# MCU-Board.net
KiCad netlist of a schematic drawn in Altium Designer
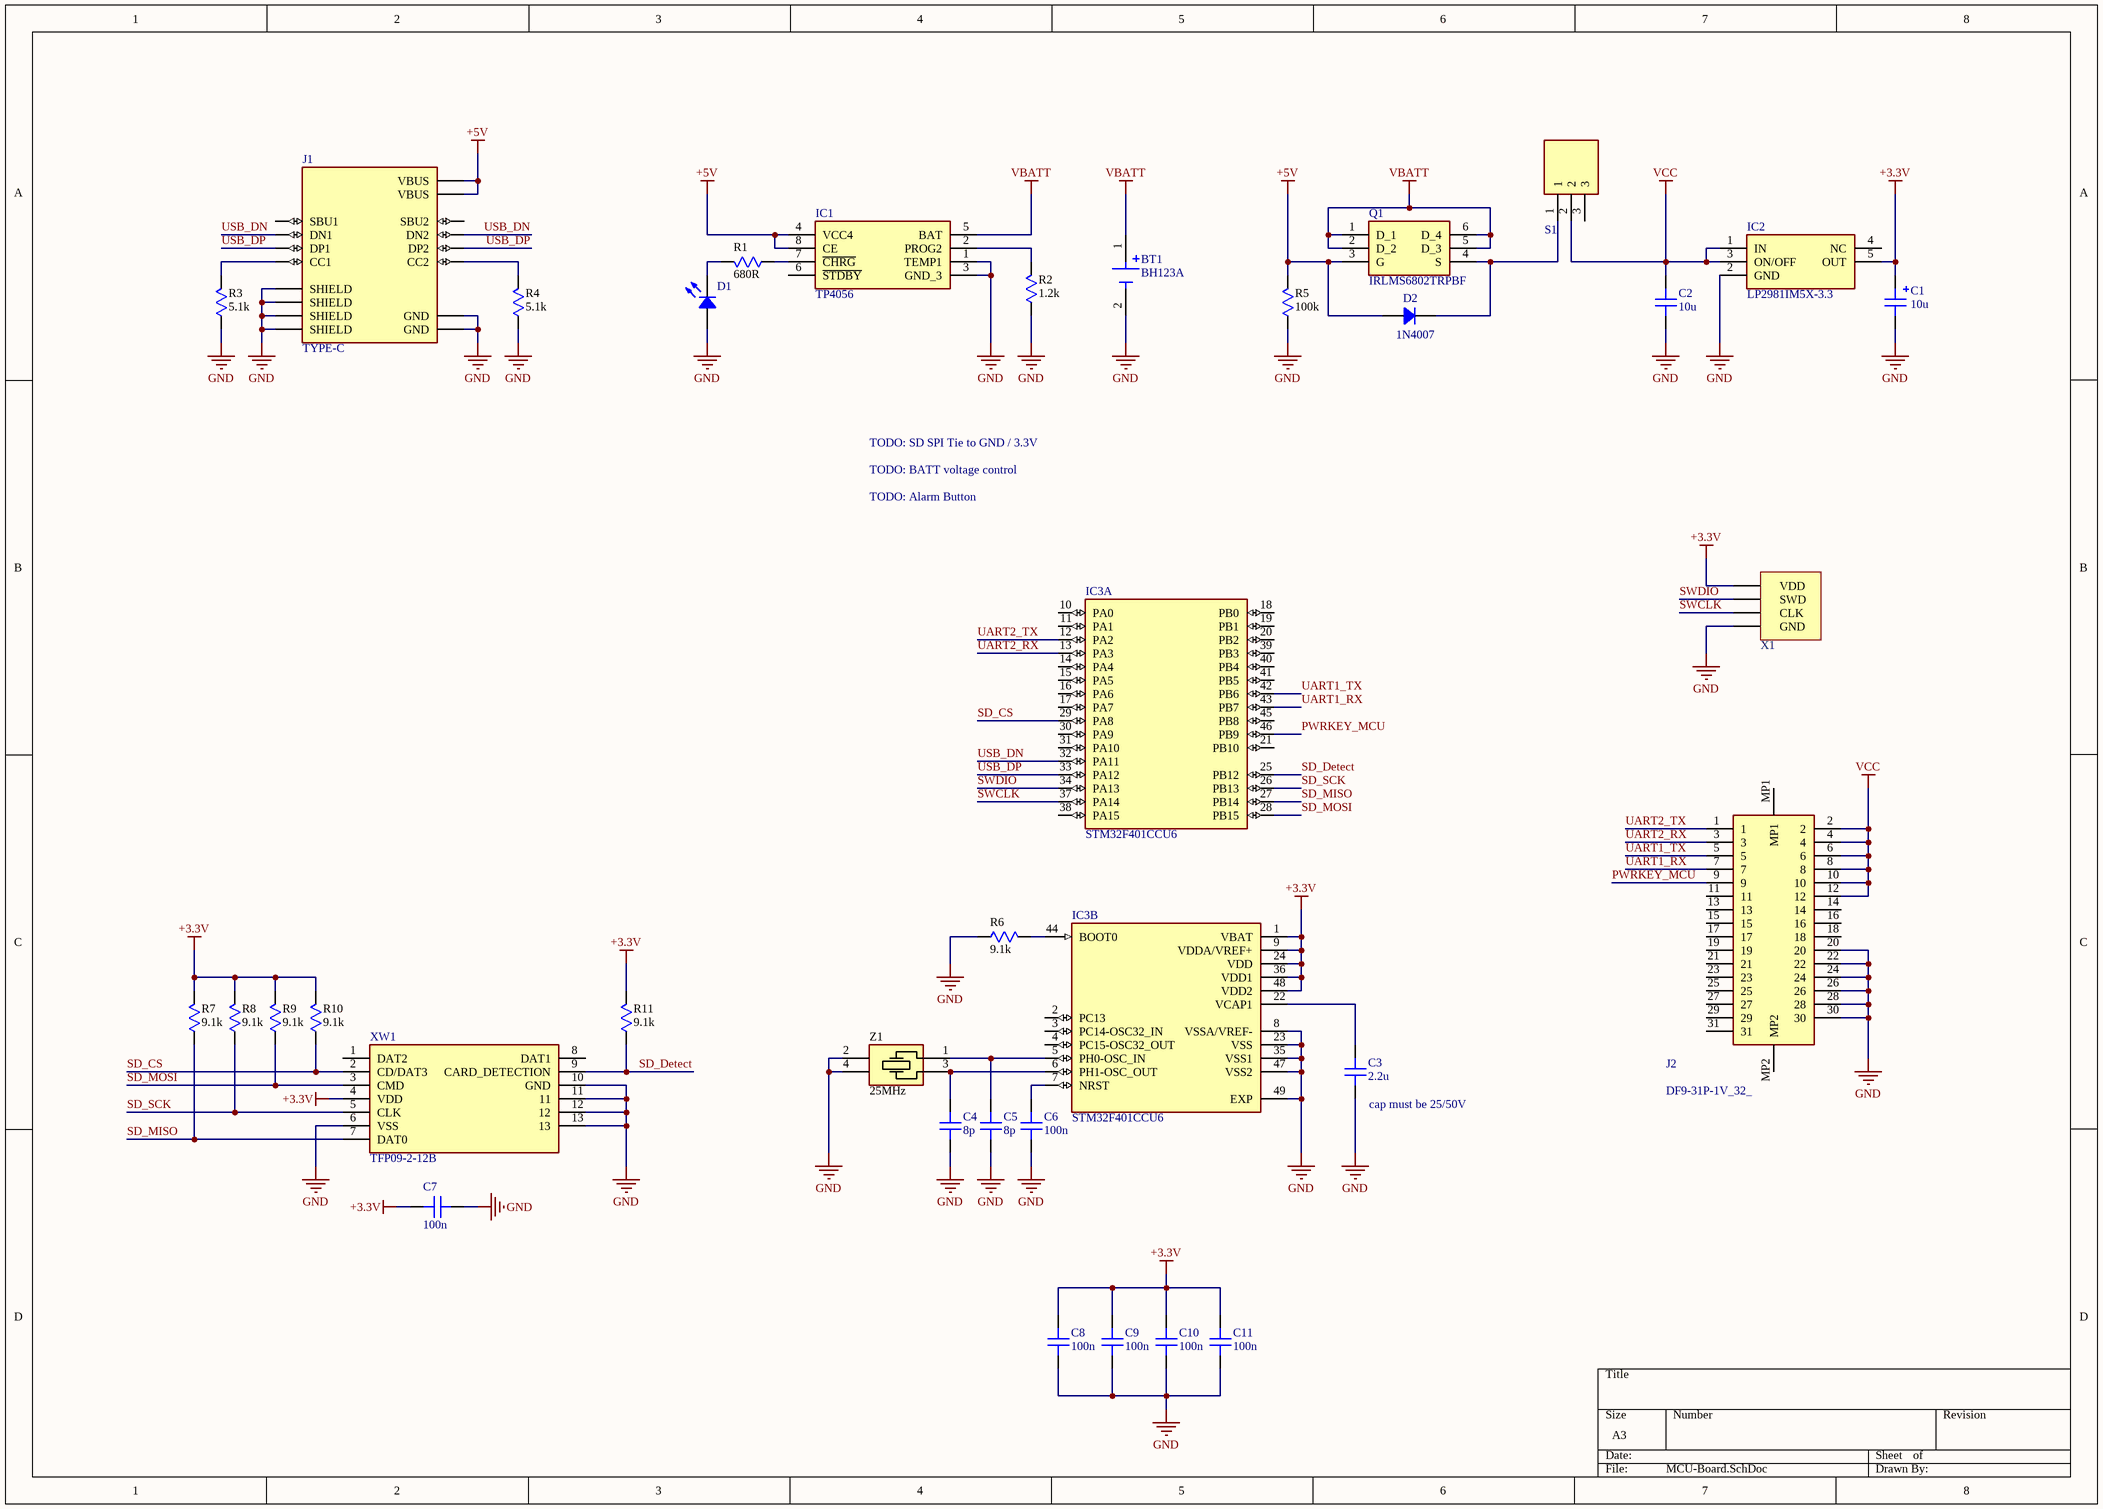
[diagram p0: MCU-Board.SchDoc]

(export (version "E")
  (design (tool "Eeschema 10.0.6"))
  (components
    (comp (ref "BT1")
      (value "BH123A")
      (footprint "BAT_BH123A")
      (description "BATTERY HOLDER CR123A PC PIN")
      (fields (field (name "MF") "MPD"))
      (libsource (lib "Schlib") (part "BH123A"))
    )
    (comp (ref "C1")
      (value "10u")
      (footprint "PcbLib:CAP: TANTAL-A")
      (description "SMD Capacitor Polar")
      (libsource (lib "Schlib") (part "Capacitor_polar"))
    )
    (comp (ref "C2")
      (value "10u")
      (footprint "PcbLib:CAP: 0805")
      (description "SMD Capacitor")
      (libsource (lib "Schlib") (part "Capacitor"))
    )
    (comp (ref "C3")
      (value "2.2u")
      (footprint "PcbLib:CAP: 0805")
      (description "SMD Capacitor")
      (libsource (lib "Schlib") (part "Capacitor"))
    )
    (comp (ref "C4")
      (value "8p")
      (footprint "PcbLib:CAP: 0603")
      (description "SMD Capacitor")
      (libsource (lib "Schlib") (part "Capacitor"))
    )
    (comp (ref "C5")
      (value "8p")
      (footprint "PcbLib:CAP: 0603")
      (description "SMD Capacitor")
      (libsource (lib "Schlib") (part "Capacitor"))
    )
    (comp (ref "C6")
      (value "100n")
      (footprint "PcbLib:CAP: 0603")
      (description "SMD Capacitor")
      (libsource (lib "Schlib") (part "Capacitor"))
    )
    (comp (ref "C7")
      (value "100n")
      (footprint "PcbLib:CAP: 0603")
      (description "SMD Capacitor")
      (libsource (lib "Schlib") (part "Capacitor"))
    )
    (comp (ref "C8")
      (value "100n")
      (footprint "PcbLib:CAP: 0603")
      (description "SMD Capacitor")
      (libsource (lib "Schlib") (part "Capacitor"))
    )
    (comp (ref "C9")
      (value "100n")
      (footprint "PcbLib:CAP: 0603")
      (description "SMD Capacitor")
      (libsource (lib "Schlib") (part "Capacitor"))
    )
    (comp (ref "C10")
      (value "100n")
      (footprint "PcbLib:CAP: 0603")
      (description "SMD Capacitor")
      (libsource (lib "Schlib") (part "Capacitor"))
    )
    (comp (ref "C11")
      (value "100n")
      (footprint "PcbLib:CAP: 0603")
      (description "SMD Capacitor")
      (libsource (lib "Schlib") (part "Capacitor"))
    )
    (comp (ref "D1")
      (value "~")
      (footprint "PcbLib:LED 0603_1608")
      (description "Chip LED")
      (libsource (lib "Schlib") (part "LED"))
    )
    (comp (ref "D2")
      (value "1N4007")
      (footprint "PcbLib:DIODE: SMA")
      (description "Rectifier Diode")
      (libsource (lib "Schlib") (part "Diode"))
    )
    (comp (ref "IC1")
      (value "TP4056")
      (footprint "PcbLib:SOIC127P600X175-9N")
      (description "Connector")
      (libsource (lib "Schlib") (part "TP4056"))
    )
    (comp (ref "IC2")
      (value "LP2981IM5X-3.3")
      (footprint "PcbLib:SOT95P280X145-5N")
      (description "Integrated Circuit")
      (fields
        (field (name "MANUFACTURER_PART_NUMBER") "LP2981IM5X-5.0")
        (field (name "MOUSER PART NUMBER") "926-LP2981IM5X-50")
      )
      (libsource (lib "Schlib") (part "LP2981IM5X-3.3"))
    )
    (comp (ref "IC3")
      (value "STM32F401CCU6")
      (footprint "PcbLib:QFN50P700X700X60-49N-D")
      (description "Integrated Circuit")
      (fields (field (name "MOUSER PART NUMBER") "511-STM32F401CCU6"))
      (libsource (lib "Schlib") (part "STM32F401CCU6"))
    )
    (comp (ref "J1")
      (value "TYPE-C")
      (footprint "PcbLib:HRO_TYPE-C-31-M-12")
      (description "USB Connectors 24 Receptacle 1 8.94*7.3mm RoHS")
      (fields (field (name "MP") "TYPE-C-31-M-12"))
      (libsource (lib "Schlib") (part "TYPE-C-31-M-12"))
    )
    (comp (ref "J2")
      (value "DF9-31P-1V_32_")
      (footprint "PcbLib:DF931P1V32")
      (description "Connector")
      (fields
        (field (name "MANUFACTURER_PART_NUMBER") "DF9-31P-1V(32)")
        (field (name "MOUSER PART NUMBER") "798-DF9-31P-1V32")
      )
      (libsource (lib "Schlib") (part "DF9-31P-1V_32_"))
    )
    (comp (ref "Q1")
      (value "IRLMS6802TRPBF")
      (footprint "PcbLib:SOT95P280X130-6N")
      (description "MOSFET (P-Channel)")
      (fields (field (name "MOUSER PART NUMBER") "942-IRLMS6802TRPBF"))
      (libsource (lib "Schlib") (part "IRLMS6802TRPBF"))
    )
    (comp (ref "R1")
      (value "680R")
      (footprint "PcbLib:RES: 0603")
      (fields
        (field (name "MANUFACTURER") "Yageo")
        (field (name "PARTNUMBER") "RC0201JR-07100RL")
        (field (name "VALUEMANUFACTURERPARTNUMBER") "Resistor film, 680R, , 0201, 0.05W, -55...+125°C")
      )
      (libsource (lib "Schlib") (part "Resistor"))
    )
    (comp (ref "R2")
      (value "1.2k")
      (footprint "PcbLib:RES: 0805")
      (fields
        (field (name "MANUFACTURER") "Yageo")
        (field (name "PARTNUMBER") "RC0201JR-07100RL")
        (field (name "VALUEMANUFACTURERPARTNUMBER") "Resistor film, 1.2k, , 0201, 0.05W, -55...+125°C")
      )
      (libsource (lib "Schlib") (part "Resistor"))
    )
    (comp (ref "R3")
      (value "5.1k")
      (footprint "PcbLib:RES: 0603")
      (fields
        (field (name "MANUFACTURER") "Yageo")
        (field (name "PARTNUMBER") "RC0201JR-07100RL")
        (field (name "VALUEMANUFACTURERPARTNUMBER") "Resistor film, 5.1k, , 0201, 0.05W, -55...+125°C")
      )
      (libsource (lib "Schlib") (part "Resistor"))
    )
    (comp (ref "R4")
      (value "5.1k")
      (footprint "PcbLib:RES: 0603")
      (fields
        (field (name "MANUFACTURER") "Yageo")
        (field (name "PARTNUMBER") "RC0201JR-07100RL")
        (field (name "VALUEMANUFACTURERPARTNUMBER") "Resistor film, 5.1k, , 0201, 0.05W, -55...+125°C")
      )
      (libsource (lib "Schlib") (part "Resistor"))
    )
    (comp (ref "R5")
      (value "100k")
      (footprint "PcbLib:RES: 0603")
      (fields
        (field (name "MANUFACTURER") "Yageo")
        (field (name "PARTNUMBER") "RC0201JR-07100RL")
        (field (name "VALUEMANUFACTURERPARTNUMBER") "Resistor film, 100k, , 0201, 0.05W, -55...+125°C")
      )
      (libsource (lib "Schlib") (part "Resistor"))
    )
    (comp (ref "R6")
      (value "9.1k")
      (footprint "PcbLib:RES: 0603")
      (fields
        (field (name "MANUFACTURER") "Yageo")
        (field (name "PARTNUMBER") "RC0201JR-07100RL")
        (field (name "VALUEMANUFACTURERPARTNUMBER") "Resistor film, 9.1k, , 0201, 0.05W, -55...+125°C")
      )
      (libsource (lib "Schlib") (part "Resistor"))
    )
    (comp (ref "R7")
      (value "9.1k")
      (footprint "PcbLib:RES: 0603")
      (fields
        (field (name "MANUFACTURER") "Yageo")
        (field (name "PARTNUMBER") "RC0201JR-07100RL")
        (field (name "VALUEMANUFACTURERPARTNUMBER") "Resistor film, 9.1k, , 0201, 0.05W, -55...+125°C")
      )
      (libsource (lib "Schlib") (part "Resistor"))
    )
    (comp (ref "R8")
      (value "9.1k")
      (footprint "PcbLib:RES: 0603")
      (fields
        (field (name "MANUFACTURER") "Yageo")
        (field (name "PARTNUMBER") "RC0201JR-07100RL")
        (field (name "VALUEMANUFACTURERPARTNUMBER") "Resistor film, 9.1k, , 0201, 0.05W, -55...+125°C")
      )
      (libsource (lib "Schlib") (part "Resistor"))
    )
    (comp (ref "R9")
      (value "9.1k")
      (footprint "PcbLib:RES: 0603")
      (fields
        (field (name "MANUFACTURER") "Yageo")
        (field (name "PARTNUMBER") "RC0201JR-07100RL")
        (field (name "VALUEMANUFACTURERPARTNUMBER") "Resistor film, 9.1k, , 0201, 0.05W, -55...+125°C")
      )
      (libsource (lib "Schlib") (part "Resistor"))
    )
    (comp (ref "R10")
      (value "9.1k")
      (footprint "PcbLib:RES: 0603")
      (fields
        (field (name "MANUFACTURER") "Yageo")
        (field (name "PARTNUMBER") "RC0201JR-07100RL")
        (field (name "VALUEMANUFACTURERPARTNUMBER") "Resistor film, 9.1k, , 0201, 0.05W, -55...+125°C")
      )
      (libsource (lib "Schlib") (part "Resistor"))
    )
    (comp (ref "R11")
      (value "9.1k")
      (footprint "PcbLib:RES: 0603")
      (fields
        (field (name "MANUFACTURER") "Yageo")
        (field (name "PARTNUMBER") "RC0201JR-07100RL")
        (field (name "VALUEMANUFACTURERPARTNUMBER") "Resistor film, 9.1k, , 0201, 0.05W, -55...+125°C")
      )
      (libsource (lib "Schlib") (part "Resistor"))
    )
    (comp (ref "S1")
      (value "OS102011MA1QN1")
      (footprint "PcbLib:OS102011MA1QN1")
      (description "Switch")
      (fields (field (name "MOUSER PART NUMBER") "611-OS102011MA1QN1"))
      (libsource (lib "Schlib") (part "OS102011MA1QN1"))
    )
    (comp (ref "X1")
      (value "~")
      (footprint "PcbLib:CON: PLS-4R")
      (description "SWD Interface")
      (libsource (lib "Schlib") (part "Connector SWD"))
    )
    (comp (ref "XW1")
      (value "TFP09-2-12B")
      (footprint "PcbLib:TFP09212B")
      (description "Connector")
      (libsource (lib "Schlib") (part "TFP09-2-12B"))
    )
    (comp (ref "Z1")
      (value "~")
      (footprint "PcbLib:OSC: 3225")
      (fields
        (field (name "MANUFACTURER") "Murata Electronics")
        (field (name "PARTNUMBER") "XRCGB25M000F0L00R0")
        (field (name "VALUEMANUFACTURERPARTNUMBER") "Crystal, 25MHz, 6pF, ±50ppm, case 2016, -30...+85°C")
        (field (name "FREQUENCY") "25MHz")
      )
      (libsource (lib "Schlib") (part "Crystal"))
    )
  )
  (nets
    (net (code "1") (name "+3.3V") (class "Default")
      (node (ref "C1") (pin "1") (pinfunction "1_1") (pintype "passive"))
      (node (ref "C10") (pin "2") (pinfunction "2_2") (pintype "passive"))
      (node (ref "C11") (pin "2") (pinfunction "2_2") (pintype "passive"))
      (node (ref "C7") (pin "2") (pinfunction "2_2") (pintype "passive"))
      (node (ref "C8") (pin "2") (pinfunction "2_2") (pintype "passive"))
      (node (ref "C9") (pin "2") (pinfunction "2_2") (pintype "passive"))
      (node (ref "IC2") (pin "5") (pinfunction "OUT_5") (pintype "passive"))
      (node (ref "IC3") (pin "1") (pinfunction "VBAT_1") (pintype "power_in"))
      (node (ref "IC3") (pin "24") (pinfunction "VDD_24") (pintype "power_in"))
      (node (ref "IC3") (pin "36") (pinfunction "VDD1_36") (pintype "power_in"))
      (node (ref "IC3") (pin "48") (pinfunction "VDD2_48") (pintype "power_in"))
      (node (ref "IC3") (pin "9") (pinfunction "VDDA/VREF+_9") (pintype "power_in"))
      (node (ref "R10") (pin "2") (pinfunction "2_2") (pintype "passive"))
      (node (ref "R11") (pin "2") (pinfunction "2_2") (pintype "passive"))
      (node (ref "R7") (pin "2") (pinfunction "2_2") (pintype "passive"))
      (node (ref "R8") (pin "2") (pinfunction "2_2") (pintype "passive"))
      (node (ref "R9") (pin "2") (pinfunction "2_2") (pintype "passive"))
      (node (ref "X1") (pin "1") (pinfunction "VDD_1") (pintype "power_in"))
      (node (ref "XW1") (pin "4") (pinfunction "VDD_4") (pintype "passive"))
    )
    (net (code "2") (name "+5V") (class "Default")
      (node (ref "D2") (pin "1") (pinfunction "1_1") (pintype "passive"))
      (node (ref "IC1") (pin "4") (pinfunction "VCC4_4") (pintype "passive"))
      (node (ref "IC1") (pin "8") (pinfunction "CE_8") (pintype "passive"))
      (node (ref "J1") (pin "A4B9") (pinfunction "VBUS_A4B9") (pintype "power_in"))
      (node (ref "J1") (pin "B4A9") (pinfunction "VBUS_B4A9") (pintype "power_in"))
      (node (ref "Q1") (pin "3") (pinfunction "G_3") (pintype "passive"))
      (node (ref "R5") (pin "2") (pinfunction "2_2") (pintype "passive"))
    )
    (net (code "3") (name "/PWRKEY_MCU") (class "Default")
      (node (ref "IC3") (pin "46") (pinfunction "PB9_46") (pintype "bidirectional"))
      (node (ref "J2") (pin "9") (pinfunction "9_9") (pintype "passive"))
    )
    (net (code "4") (name "/SD_CS") (class "Default")
      (node (ref "IC3") (pin "29") (pinfunction "PA8_29") (pintype "bidirectional"))
      (node (ref "R10") (pin "1") (pinfunction "1_1") (pintype "passive"))
      (node (ref "XW1") (pin "2") (pinfunction "CD/DAT3_2") (pintype "passive"))
    )
    (net (code "5") (name "/SD_Detect") (class "Default")
      (node (ref "IC3") (pin "25") (pinfunction "PB12_25") (pintype "bidirectional"))
      (node (ref "R11") (pin "1") (pinfunction "1_1") (pintype "passive"))
      (node (ref "XW1") (pin "9") (pinfunction "CARD_DETECTION_9") (pintype "passive"))
    )
    (net (code "6") (name "/SD_MISO") (class "Default")
      (node (ref "IC3") (pin "27") (pinfunction "PB14_27") (pintype "bidirectional"))
      (node (ref "R7") (pin "1") (pinfunction "1_1") (pintype "passive"))
      (node (ref "XW1") (pin "7") (pinfunction "DAT0_7") (pintype "passive"))
    )
    (net (code "7") (name "/SD_MOSI") (class "Default")
      (node (ref "IC3") (pin "28") (pinfunction "PB15_28") (pintype "bidirectional"))
      (node (ref "R9") (pin "1") (pinfunction "1_1") (pintype "passive"))
      (node (ref "XW1") (pin "3") (pinfunction "CMD_3") (pintype "passive"))
    )
    (net (code "8") (name "/SD_SCK") (class "Default")
      (node (ref "IC3") (pin "26") (pinfunction "PB13_26") (pintype "bidirectional"))
      (node (ref "R8") (pin "1") (pinfunction "1_1") (pintype "passive"))
      (node (ref "XW1") (pin "5") (pinfunction "CLK_5") (pintype "passive"))
    )
    (net (code "9") (name "/SWCLK") (class "Default")
      (node (ref "IC3") (pin "37") (pinfunction "PA14_37") (pintype "bidirectional"))
      (node (ref "X1") (pin "3") (pinfunction "CLK_3") (pintype "passive"))
    )
    (net (code "10") (name "/SWDIO") (class "Default")
      (node (ref "IC3") (pin "34") (pinfunction "PA13_34") (pintype "bidirectional"))
      (node (ref "X1") (pin "2") (pinfunction "SWD_2") (pintype "passive"))
    )
    (net (code "11") (name "/UART1_RX") (class "Default")
      (node (ref "IC3") (pin "43") (pinfunction "PB7_43") (pintype "bidirectional"))
      (node (ref "J2") (pin "7") (pinfunction "7_7") (pintype "passive"))
    )
    (net (code "12") (name "/UART1_TX") (class "Default")
      (node (ref "IC3") (pin "42") (pinfunction "PB6_42") (pintype "bidirectional"))
      (node (ref "J2") (pin "5") (pinfunction "5_5") (pintype "passive"))
    )
    (net (code "13") (name "/UART2_RX") (class "Default")
      (node (ref "IC3") (pin "13") (pinfunction "PA3_13") (pintype "bidirectional"))
      (node (ref "J2") (pin "3") (pinfunction "3_3") (pintype "passive"))
    )
    (net (code "14") (name "/UART2_TX") (class "Default")
      (node (ref "IC3") (pin "12") (pinfunction "PA2_12") (pintype "bidirectional"))
      (node (ref "J2") (pin "1") (pinfunction "1_1") (pintype "passive"))
    )
    (net (code "15") (name "/USB_DN") (class "Default")
      (node (ref "IC3") (pin "32") (pinfunction "PA11_32") (pintype "bidirectional"))
      (node (ref "J1") (pin "A7") (pinfunction "DN1_A7") (pintype "bidirectional"))
      (node (ref "J1") (pin "B7") (pinfunction "DN2_B7") (pintype "bidirectional"))
    )
    (net (code "16") (name "/USB_DP") (class "Default")
      (node (ref "IC3") (pin "33") (pinfunction "PA12_33") (pintype "bidirectional"))
      (node (ref "J1") (pin "A6") (pinfunction "DP1_A6") (pintype "bidirectional"))
      (node (ref "J1") (pin "B6") (pinfunction "DP2_B6") (pintype "bidirectional"))
    )
    (net (code "17") (name "GND") (class "Default")
      (node (ref "BT1") (pin "2") (pinfunction "NEG_2") (pintype "passive"))
      (node (ref "C1") (pin "2") (pinfunction "2_2") (pintype "passive"))
      (node (ref "C10") (pin "1") (pinfunction "1_1") (pintype "passive"))
      (node (ref "C11") (pin "1") (pinfunction "1_1") (pintype "passive"))
      (node (ref "C2") (pin "1") (pinfunction "1_1") (pintype "passive"))
      (node (ref "C3") (pin "1") (pinfunction "1_1") (pintype "passive"))
      (node (ref "C4") (pin "1") (pinfunction "1_1") (pintype "passive"))
      (node (ref "C5") (pin "2") (pinfunction "2_2") (pintype "passive"))
      (node (ref "C6") (pin "1") (pinfunction "1_1") (pintype "passive"))
      (node (ref "C7") (pin "1") (pinfunction "1_1") (pintype "passive"))
      (node (ref "C8") (pin "1") (pinfunction "1_1") (pintype "passive"))
      (node (ref "C9") (pin "1") (pinfunction "1_1") (pintype "passive"))
      (node (ref "D1") (pin "1") (pinfunction "1_1") (pintype "passive"))
      (node (ref "IC1") (pin "1") (pinfunction "TEMP1_1") (pintype "passive"))
      (node (ref "IC1") (pin "3") (pinfunction "GND_3_3") (pintype "passive"))
      (node (ref "IC2") (pin "2") (pinfunction "GND_2") (pintype "passive"))
      (node (ref "IC3") (pin "23") (pinfunction "VSS_23") (pintype "power_in"))
      (node (ref "IC3") (pin "35") (pinfunction "VSS1_35") (pintype "power_in"))
      (node (ref "IC3") (pin "47") (pinfunction "VSS2_47") (pintype "power_in"))
      (node (ref "IC3") (pin "49") (pinfunction "EXP_49") (pintype "power_in"))
      (node (ref "IC3") (pin "8") (pinfunction "VSSA/VREF-_8") (pintype "power_in"))
      (node (ref "J1") (pin "A1B12") (pinfunction "GND_A1B12") (pintype "power_in"))
      (node (ref "J1") (pin "B1A12") (pinfunction "GND_B1A12") (pintype "power_in"))
      (node (ref "J1") (pin "S1") (pinfunction "SHIELD_S1") (pintype "passive"))
      (node (ref "J1") (pin "S2") (pinfunction "SHIELD_S2") (pintype "passive"))
      (node (ref "J1") (pin "S3") (pinfunction "SHIELD_S3") (pintype "passive"))
      (node (ref "J1") (pin "S4") (pinfunction "SHIELD_S4") (pintype "passive"))
      (node (ref "J2") (pin "20") (pinfunction "20_20") (pintype "passive"))
      (node (ref "J2") (pin "22") (pinfunction "22_22") (pintype "passive"))
      (node (ref "J2") (pin "24") (pinfunction "24_24") (pintype "passive"))
      (node (ref "J2") (pin "26") (pinfunction "26_26") (pintype "passive"))
      (node (ref "J2") (pin "28") (pinfunction "28_28") (pintype "passive"))
      (node (ref "J2") (pin "30") (pinfunction "30_30") (pintype "passive"))
      (node (ref "R2") (pin "1") (pinfunction "1_1") (pintype "passive"))
      (node (ref "R3") (pin "1") (pinfunction "1_1") (pintype "passive"))
      (node (ref "R4") (pin "1") (pinfunction "1_1") (pintype "passive"))
      (node (ref "R5") (pin "1") (pinfunction "1_1") (pintype "passive"))
      (node (ref "R6") (pin "1") (pinfunction "1_1") (pintype "passive"))
      (node (ref "X1") (pin "4") (pinfunction "GND_4") (pintype "power_in"))
      (node (ref "XW1") (pin "10") (pinfunction "GND_10") (pintype "passive"))
      (node (ref "XW1") (pin "11") (pinfunction "11_11") (pintype "passive"))
      (node (ref "XW1") (pin "12") (pinfunction "12_12") (pintype "passive"))
      (node (ref "XW1") (pin "13") (pinfunction "13_13") (pintype "passive"))
      (node (ref "XW1") (pin "6") (pinfunction "VSS_6") (pintype "passive"))
      (node (ref "Z1") (pin "2") (pinfunction "2_2") (pintype "passive"))
      (node (ref "Z1") (pin "4") (pinfunction "4_4") (pintype "passive"))
    )
    (net (code "18") (name "Net-(D1-Pad2)") (class "Default")
      (node (ref "D1") (pin "2") (pinfunction "2_2") (pintype "passive"))
      (node (ref "R1") (pin "2") (pinfunction "2_2") (pintype "passive"))
    )
    (net (code "19") (name "Net-(IC1-PROG2)") (class "Default")
      (node (ref "IC1") (pin "2") (pinfunction "PROG2_2") (pintype "passive"))
      (node (ref "R2") (pin "2") (pinfunction "2_2") (pintype "passive"))
    )
    (net (code "20") (name "Net-(IC1-~{CHRG})") (class "Default")
      (node (ref "IC1") (pin "7") (pinfunction "~{CHRG}_7") (pintype "passive"))
      (node (ref "R1") (pin "1") (pinfunction "1_1") (pintype "passive"))
    )
    (net (code "21") (name "Net-(IC3B-BOOT0)") (class "Default")
      (node (ref "IC3") (pin "44") (pinfunction "BOOT0_44") (pintype "input"))
      (node (ref "R6") (pin "2") (pinfunction "2_2") (pintype "passive"))
    )
    (net (code "22") (name "Net-(IC3B-NRST)") (class "Default")
      (node (ref "C6") (pin "2") (pinfunction "2_2") (pintype "passive"))
      (node (ref "IC3") (pin "7") (pinfunction "NRST_7") (pintype "bidirectional"))
    )
    (net (code "23") (name "Net-(IC3B-PH0-OSC_IN)") (class "Default")
      (node (ref "C5") (pin "1") (pinfunction "1_1") (pintype "passive"))
      (node (ref "IC3") (pin "5") (pinfunction "PH0-OSC_IN_5") (pintype "bidirectional"))
      (node (ref "Z1") (pin "1") (pinfunction "1_1") (pintype "passive"))
    )
    (net (code "24") (name "Net-(IC3B-PH1-OSC_OUT)") (class "Default")
      (node (ref "C4") (pin "2") (pinfunction "2_2") (pintype "passive"))
      (node (ref "IC3") (pin "6") (pinfunction "PH1-OSC_OUT_6") (pintype "bidirectional"))
      (node (ref "Z1") (pin "3") (pinfunction "3_3") (pintype "passive"))
    )
    (net (code "25") (name "Net-(IC3B-VCAP1)") (class "Default")
      (node (ref "C3") (pin "2") (pinfunction "2_2") (pintype "passive"))
      (node (ref "IC3") (pin "22") (pinfunction "VCAP1_22") (pintype "power_in"))
    )
    (net (code "26") (name "Net-(J1-CC1)") (class "Default")
      (node (ref "J1") (pin "A5") (pinfunction "CC1_A5") (pintype "bidirectional"))
      (node (ref "R3") (pin "2") (pinfunction "2_2") (pintype "passive"))
    )
    (net (code "27") (name "Net-(J1-CC2)") (class "Default")
      (node (ref "J1") (pin "B5") (pinfunction "CC2_B5") (pintype "bidirectional"))
      (node (ref "R4") (pin "2") (pinfunction "2_2") (pintype "passive"))
    )
    (net (code "28") (name "Net-(Q1-S)") (class "Default")
      (node (ref "D2") (pin "2") (pinfunction "2_2") (pintype "passive"))
      (node (ref "Q1") (pin "4") (pinfunction "S_4") (pintype "passive"))
      (node (ref "S1") (pin "1") (pinfunction "1_1") (pintype "passive"))
    )
    (net (code "29") (name "VBATT") (class "Default")
      (node (ref "BT1") (pin "1") (pinfunction "POS_1") (pintype "passive"))
      (node (ref "IC1") (pin "5") (pinfunction "BAT_5") (pintype "passive"))
      (node (ref "Q1") (pin "1") (pinfunction "D_1_1") (pintype "passive"))
      (node (ref "Q1") (pin "2") (pinfunction "D_2_2") (pintype "passive"))
      (node (ref "Q1") (pin "5") (pinfunction "D_3_5") (pintype "passive"))
      (node (ref "Q1") (pin "6") (pinfunction "D_4_6") (pintype "passive"))
    )
    (net (code "30") (name "VCC") (class "Default")
      (node (ref "C2") (pin "2") (pinfunction "2_2") (pintype "passive"))
      (node (ref "IC2") (pin "1") (pinfunction "IN_1") (pintype "passive"))
      (node (ref "IC2") (pin "3") (pinfunction "ON/OFF_3") (pintype "passive"))
      (node (ref "J2") (pin "10") (pinfunction "10_10") (pintype "passive"))
      (node (ref "J2") (pin "12") (pinfunction "12_12") (pintype "passive"))
      (node (ref "J2") (pin "2") (pinfunction "2_2") (pintype "passive"))
      (node (ref "J2") (pin "4") (pinfunction "4_4") (pintype "passive"))
      (node (ref "J2") (pin "6") (pinfunction "6_6") (pintype "passive"))
      (node (ref "J2") (pin "8") (pinfunction "8_8") (pintype "passive"))
      (node (ref "S1") (pin "2") (pinfunction "2_2") (pintype "passive"))
    )
    (net (code "31") (name "unconnected-(IC1-~{STDBY}-Pad6)") (class "Default")
      (node (ref "IC1") (pin "6") (pinfunction "~{STDBY}_6") (pintype "passive"))
    )
    (net (code "32") (name "unconnected-(IC2-NC-Pad4)") (class "Default")
      (node (ref "IC2") (pin "4") (pinfunction "NC_4") (pintype "passive"))
    )
    (net (code "33") (name "unconnected-(IC3A-PA0-Pad10)") (class "Default")
      (node (ref "IC3") (pin "10") (pinfunction "PA0_10") (pintype "bidirectional"))
    )
    (net (code "34") (name "unconnected-(IC3A-PA1-Pad11)") (class "Default")
      (node (ref "IC3") (pin "11") (pinfunction "PA1_11") (pintype "bidirectional"))
    )
    (net (code "35") (name "unconnected-(IC3A-PA4-Pad14)") (class "Default")
      (node (ref "IC3") (pin "14") (pinfunction "PA4_14") (pintype "bidirectional"))
    )
    (net (code "36") (name "unconnected-(IC3A-PA5-Pad15)") (class "Default")
      (node (ref "IC3") (pin "15") (pinfunction "PA5_15") (pintype "bidirectional"))
    )
    (net (code "37") (name "unconnected-(IC3A-PA6-Pad16)") (class "Default")
      (node (ref "IC3") (pin "16") (pinfunction "PA6_16") (pintype "bidirectional"))
    )
    (net (code "38") (name "unconnected-(IC3A-PA7-Pad17)") (class "Default")
      (node (ref "IC3") (pin "17") (pinfunction "PA7_17") (pintype "bidirectional"))
    )
    (net (code "39") (name "unconnected-(IC3A-PA9-Pad30)") (class "Default")
      (node (ref "IC3") (pin "30") (pinfunction "PA9_30") (pintype "bidirectional"))
    )
    (net (code "40") (name "unconnected-(IC3A-PA10-Pad31)") (class "Default")
      (node (ref "IC3") (pin "31") (pinfunction "PA10_31") (pintype "bidirectional"))
    )
    (net (code "41") (name "unconnected-(IC3A-PA15-Pad38)") (class "Default")
      (node (ref "IC3") (pin "38") (pinfunction "PA15_38") (pintype "bidirectional"))
    )
    (net (code "42") (name "unconnected-(IC3A-PB0-Pad18)") (class "Default")
      (node (ref "IC3") (pin "18") (pinfunction "PB0_18") (pintype "bidirectional"))
    )
    (net (code "43") (name "unconnected-(IC3A-PB1-Pad19)") (class "Default")
      (node (ref "IC3") (pin "19") (pinfunction "PB1_19") (pintype "bidirectional"))
    )
    (net (code "44") (name "unconnected-(IC3A-PB2-Pad20)") (class "Default")
      (node (ref "IC3") (pin "20") (pinfunction "PB2_20") (pintype "bidirectional"))
    )
    (net (code "45") (name "unconnected-(IC3A-PB3-Pad39)") (class "Default")
      (node (ref "IC3") (pin "39") (pinfunction "PB3_39") (pintype "bidirectional"))
    )
    (net (code "46") (name "unconnected-(IC3A-PB4-Pad40)") (class "Default")
      (node (ref "IC3") (pin "40") (pinfunction "PB4_40") (pintype "bidirectional"))
    )
    (net (code "47") (name "unconnected-(IC3A-PB5-Pad41)") (class "Default")
      (node (ref "IC3") (pin "41") (pinfunction "PB5_41") (pintype "bidirectional"))
    )
    (net (code "48") (name "unconnected-(IC3A-PB8-Pad45)") (class "Default")
      (node (ref "IC3") (pin "45") (pinfunction "PB8_45") (pintype "bidirectional"))
    )
    (net (code "49") (name "unconnected-(IC3A-PB10-Pad21)") (class "Default")
      (node (ref "IC3") (pin "21") (pinfunction "PB10_21") (pintype "bidirectional"))
    )
    (net (code "50") (name "unconnected-(IC3B-PC13-Pad2)") (class "Default")
      (node (ref "IC3") (pin "2") (pinfunction "PC13_2") (pintype "bidirectional"))
    )
    (net (code "51") (name "unconnected-(IC3B-PC14-OSC32_IN-Pad3)") (class "Default")
      (node (ref "IC3") (pin "3") (pinfunction "PC14-OSC32_IN_3") (pintype "bidirectional"))
    )
    (net (code "52") (name "unconnected-(IC3B-PC15-OSC32_OUT-Pad4)") (class "Default")
      (node (ref "IC3") (pin "4") (pinfunction "PC15-OSC32_OUT_4") (pintype "bidirectional"))
    )
    (net (code "53") (name "unconnected-(J1-SBU1-PadA8)") (class "Default")
      (node (ref "J1") (pin "A8") (pinfunction "SBU1_A8") (pintype "bidirectional"))
    )
    (net (code "54") (name "unconnected-(J1-SBU2-PadB8)") (class "Default")
      (node (ref "J1") (pin "B8") (pinfunction "SBU2_B8") (pintype "bidirectional"))
    )
    (net (code "55") (name "unconnected-(J2-Pad11)") (class "Default")
      (node (ref "J2") (pin "11") (pinfunction "11_11") (pintype "passive"))
    )
    (net (code "56") (name "unconnected-(J2-Pad13)") (class "Default")
      (node (ref "J2") (pin "13") (pinfunction "13_13") (pintype "passive"))
    )
    (net (code "57") (name "unconnected-(J2-Pad14)") (class "Default")
      (node (ref "J2") (pin "14") (pinfunction "14_14") (pintype "passive"))
    )
    (net (code "58") (name "unconnected-(J2-Pad15)") (class "Default")
      (node (ref "J2") (pin "15") (pinfunction "15_15") (pintype "passive"))
    )
    (net (code "59") (name "unconnected-(J2-Pad16)") (class "Default")
      (node (ref "J2") (pin "16") (pinfunction "16_16") (pintype "passive"))
    )
    (net (code "60") (name "unconnected-(J2-Pad17)") (class "Default")
      (node (ref "J2") (pin "17") (pinfunction "17_17") (pintype "passive"))
    )
    (net (code "61") (name "unconnected-(J2-Pad18)") (class "Default")
      (node (ref "J2") (pin "18") (pinfunction "18_18") (pintype "passive"))
    )
    (net (code "62") (name "unconnected-(J2-Pad19)") (class "Default")
      (node (ref "J2") (pin "19") (pinfunction "19_19") (pintype "passive"))
    )
    (net (code "63") (name "unconnected-(J2-Pad21)") (class "Default")
      (node (ref "J2") (pin "21") (pinfunction "21_21") (pintype "passive"))
    )
    (net (code "64") (name "unconnected-(J2-Pad23)") (class "Default")
      (node (ref "J2") (pin "23") (pinfunction "23_23") (pintype "passive"))
    )
    (net (code "65") (name "unconnected-(J2-Pad25)") (class "Default")
      (node (ref "J2") (pin "25") (pinfunction "25_25") (pintype "passive"))
    )
    (net (code "66") (name "unconnected-(J2-Pad27)") (class "Default")
      (node (ref "J2") (pin "27") (pinfunction "27_27") (pintype "passive"))
    )
    (net (code "67") (name "unconnected-(J2-Pad29)") (class "Default")
      (node (ref "J2") (pin "29") (pinfunction "29_29") (pintype "passive"))
    )
    (net (code "68") (name "unconnected-(J2-Pad31)") (class "Default")
      (node (ref "J2") (pin "31") (pinfunction "31_31") (pintype "passive"))
    )
    (net (code "69") (name "unconnected-(J2-PadMP1)") (class "Default")
      (node (ref "J2") (pin "MP1") (pinfunction "MP1_MP1") (pintype "passive"))
    )
    (net (code "70") (name "unconnected-(J2-PadMP2)") (class "Default")
      (node (ref "J2") (pin "MP2") (pinfunction "MP2_MP2") (pintype "passive"))
    )
    (net (code "71") (name "unconnected-(S1-Pad3)") (class "Default")
      (node (ref "S1") (pin "3") (pinfunction "3_3") (pintype "passive"))
    )
    (net (code "72") (name "unconnected-(XW1-DAT1-Pad8)") (class "Default")
      (node (ref "XW1") (pin "8") (pinfunction "DAT1_8") (pintype "passive"))
    )
    (net (code "73") (name "unconnected-(XW1-DAT2-Pad1)") (class "Default")
      (node (ref "XW1") (pin "1") (pinfunction "DAT2_1") (pintype "passive"))
    )
  )
)
